# 60_Inkremental.net
KiCad netlist of a schematic drawn in Altium Designer
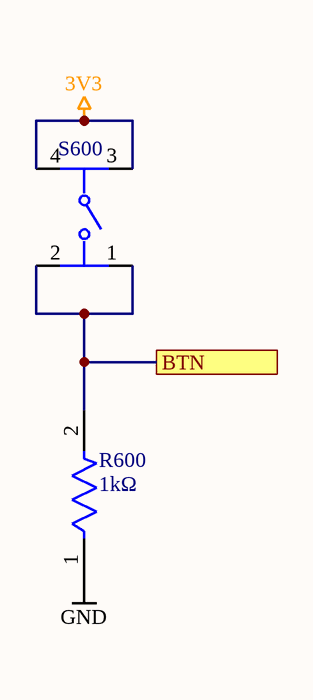
[diagram p0: 60_Inkremental.SchDoc]

(export (version "E")
  (design (tool "Eeschema 10.0.6"))
  (components
    (comp (ref "R600")
      (value "1kΩ")
      (footprint "FP-CRCW0603-e3-MFG")
      (description "RES Thick Film, 1kΩ, 1%, 0.1W, 100ppm/°C, 0603, CRCW06031K00FKEA")
      (fields (field (name "TOLERANCE") "1%"))
      (libsource (lib "Altium Content Vault") (part "1029c3af85768c4190bb7ad29bc67b5"))
    )
    (comp (ref "S600")
      (value "~")
      (footprint "FP-PTS645SM43SMTR92LFS-MFG")
      (description "SWITCH TACTILE SPST-NO 0.05A 12V\r\nPTS645SM43SMTR92LFS")
      (libsource (lib "Altium Content Vault") (part "1adf0dd01260c80cf25a44bfd6b99ba"))
    )
  )
  (nets
    (net (code "1") (name "/BTN") (class "Default")
      (node (ref "R600") (pin "2") (pinfunction "2_2") (pintype "passive"))
      (node (ref "S600") (pin "1") (pinfunction "1_1") (pintype "passive"))
      (node (ref "S600") (pin "2") (pinfunction "2_2") (pintype "passive"))
    )
    (net (code "2") (name "3V3") (class "Default")
      (node (ref "S600") (pin "3") (pinfunction "3_3") (pintype "passive"))
      (node (ref "S600") (pin "4") (pinfunction "4_4") (pintype "passive"))
    )
    (net (code "3") (name "GND") (class "Default")
      (node (ref "R600") (pin "1") (pinfunction "1_1") (pintype "passive"))
    )
  )
)
